# Challenger-2040.net
KiCad netlist of a schematic drawn in EAGLE
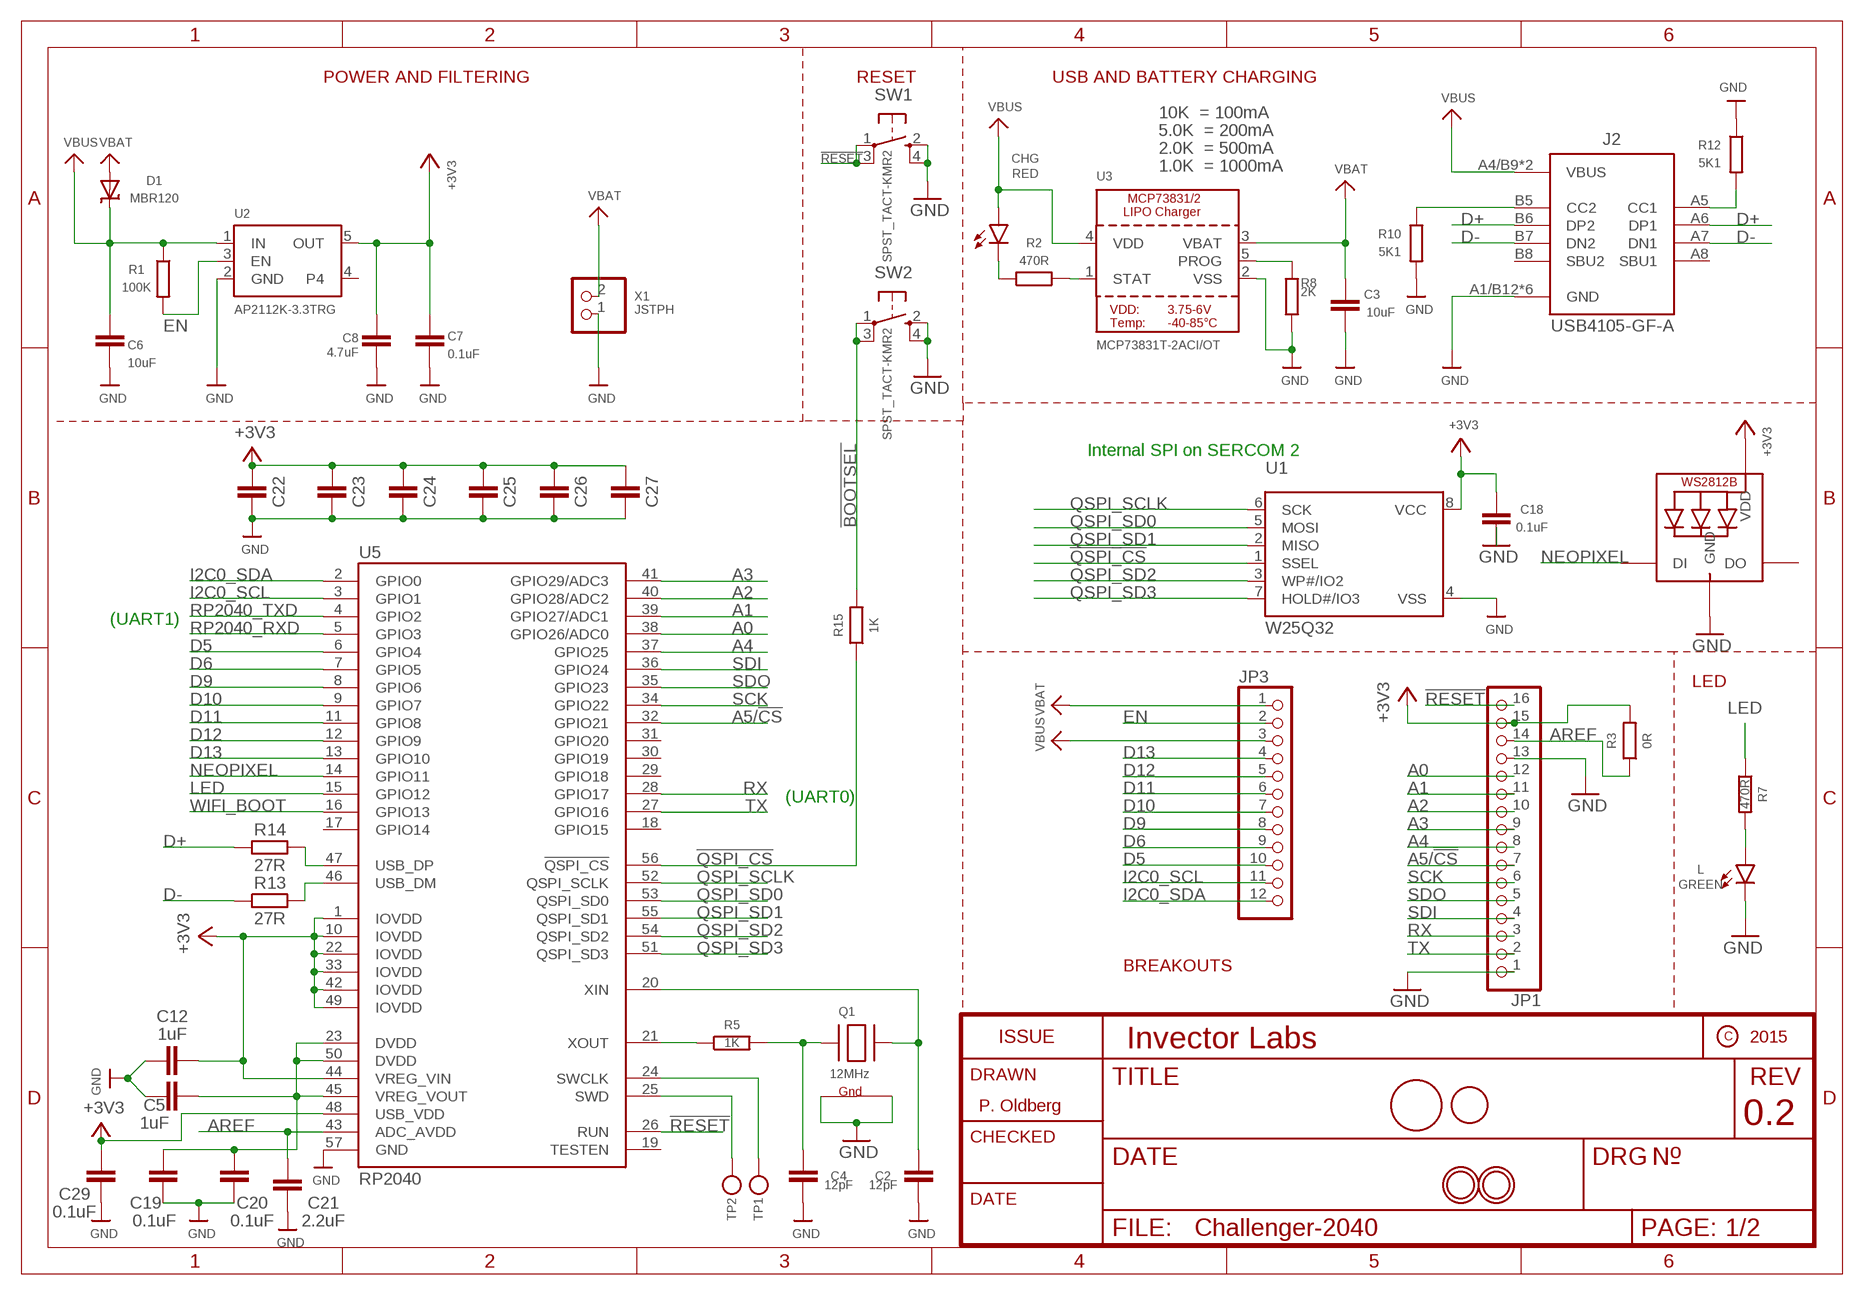
[diagram p0: schematic, sheet 1]
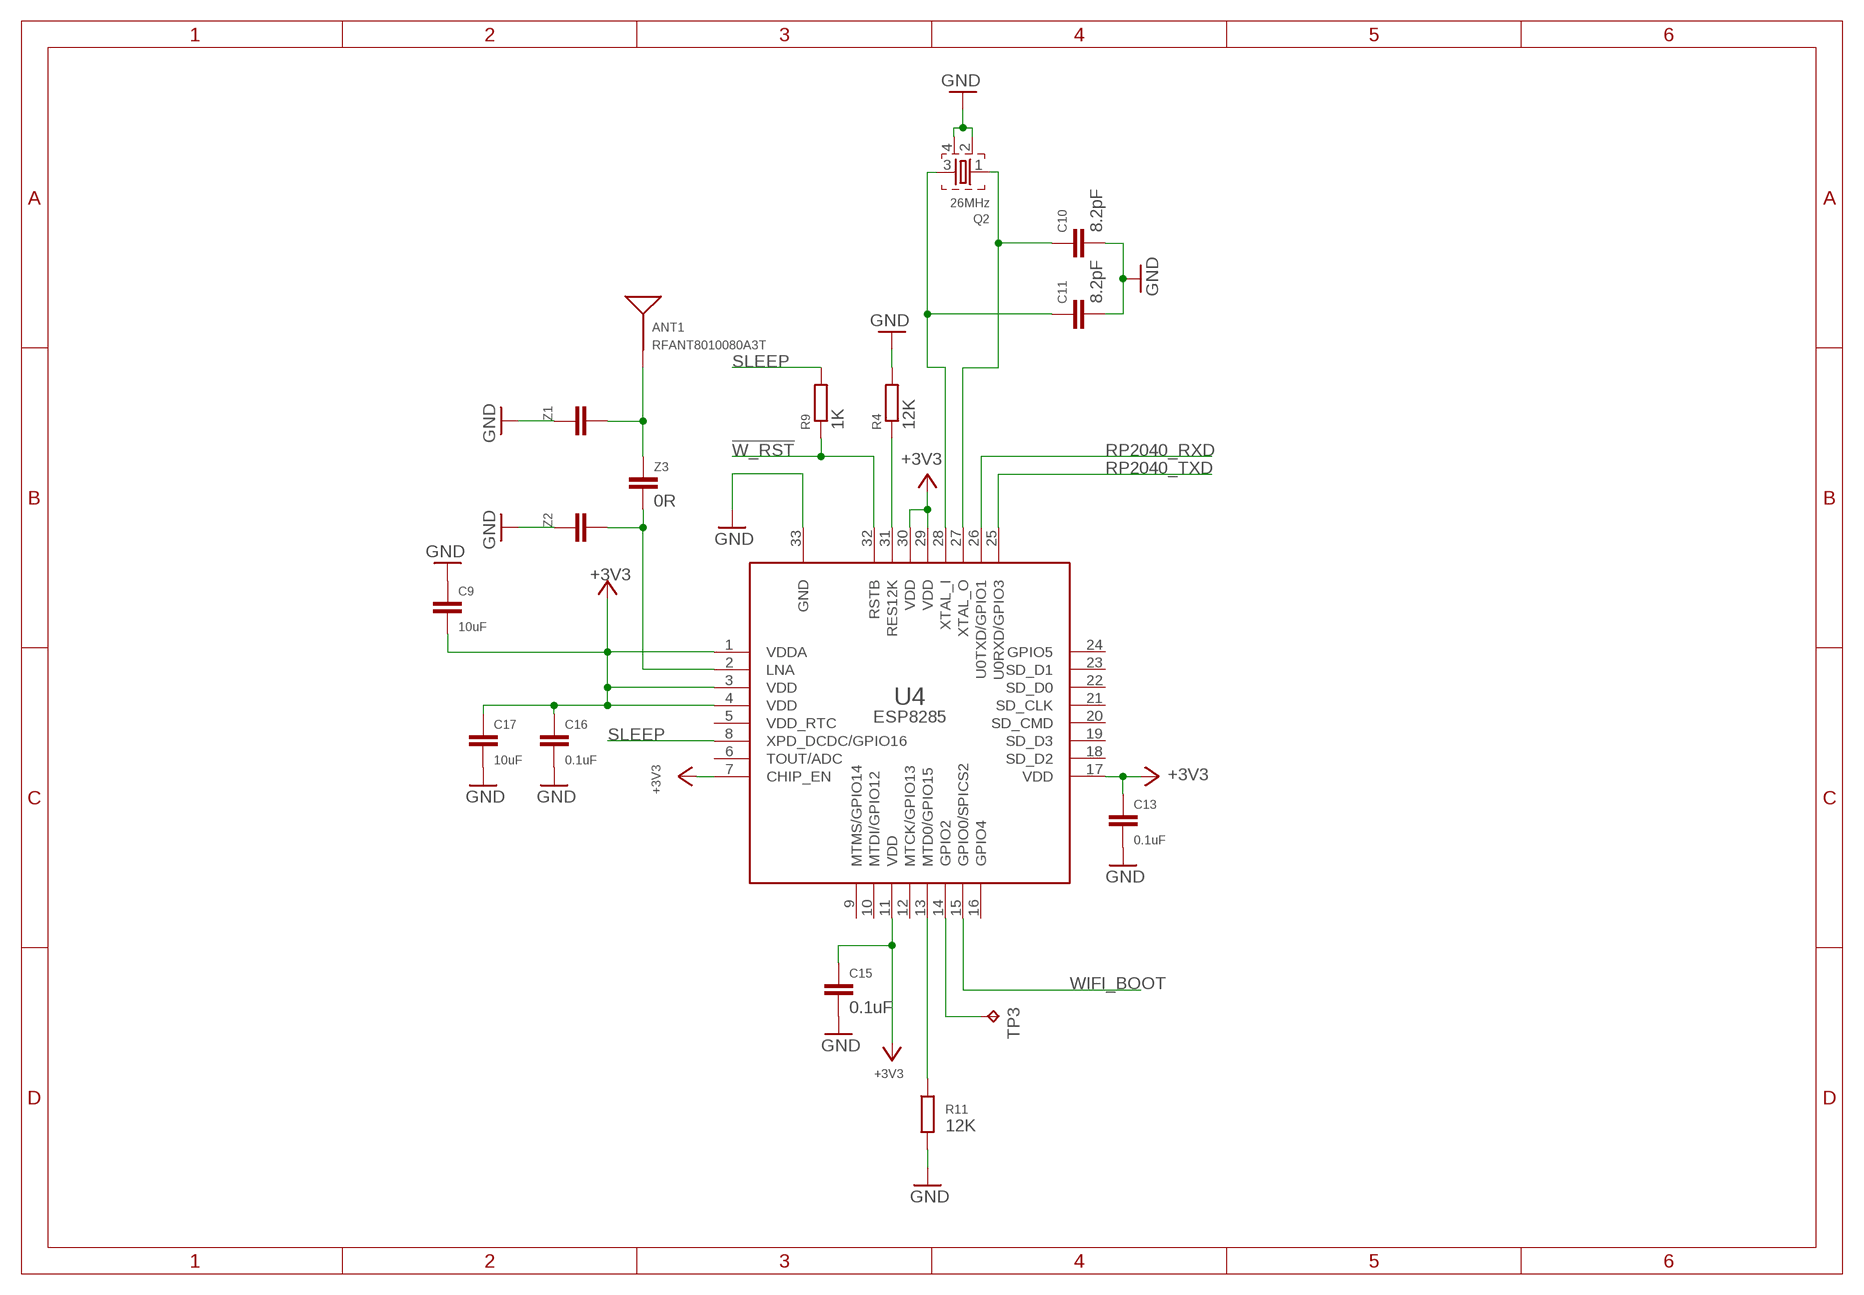
[diagram p1: schematic, sheet 2]

(export (version "E")
  (design (tool "Eeschema 10.0.6"))
  (components
    (comp (ref "ANT1")
      (value "RFANT8010080A3T")
      (footprint "eagle-import:ANTENNA-CHIP6")
      (libsource (lib "eagle-import") (part "ANTENNA2SMD6"))
    )
    (comp (ref "C9")
      (value "10uF")
      (footprint "eagle-import:CAPC1608X85")
      (libsource (lib "eagle-import") (part "CCHIP-0603(1608-METRIC)_"))
    )
    (comp (ref "C10")
      (value "8.2pF")
      (footprint "eagle-import:CAPC1005X60")
      (libsource (lib "eagle-import") (part "CCHIP-0402(1005-METRIC)_"))
    )
    (comp (ref "C11")
      (value "8.2pF")
      (footprint "eagle-import:CAPC1005X60")
      (libsource (lib "eagle-import") (part "CCHIP-0402(1005-METRIC)_"))
    )
    (comp (ref "C13")
      (value "0.1uF")
      (footprint "eagle-import:CAPC1005X60")
      (libsource (lib "eagle-import") (part "CCHIP-0402(1005-METRIC)_"))
    )
    (comp (ref "C15")
      (value "0.1uF")
      (footprint "eagle-import:CAPC1005X60")
      (libsource (lib "eagle-import") (part "CCHIP-0402(1005-METRIC)_"))
    )
    (comp (ref "C16")
      (value "0.1uF")
      (footprint "eagle-import:CAPC1005X60")
      (libsource (lib "eagle-import") (part "CCHIP-0402(1005-METRIC)_"))
    )
    (comp (ref "C17")
      (value "10uF")
      (footprint "eagle-import:CAPC1608X85")
      (libsource (lib "eagle-import") (part "CCHIP-0603(1608-METRIC)_"))
    )
    (comp (ref "Q2")
      (value "26MHz")
      (footprint "eagle-import:FA-128")
      (libsource (lib "eagle-import") (part "FA-128"))
    )
    (comp (ref "R4")
      (value "12K")
      (footprint "eagle-import:RESC1005X40")
      (libsource (lib "eagle-import") (part "RCHIP-0402(1005-METRIC)_"))
    )
    (comp (ref "R9")
      (value "1K")
      (footprint "eagle-import:RESC1005X40")
      (libsource (lib "eagle-import") (part "RCHIP-0402(1005-METRIC)_"))
    )
    (comp (ref "R11")
      (value "12K")
      (footprint "eagle-import:RESC1005X40")
      (libsource (lib "eagle-import") (part "RCHIP-0402(1005-METRIC)_"))
    )
    (comp (ref "TP3")
      (value "TPB1,27")
      (footprint "eagle-import:B1,27")
      (libsource (lib "eagle-import") (part "TPB1,27"))
    )
    (comp (ref "U4")
      (value "ESP8285")
      (footprint "eagle-import:SLP32")
      (libsource (lib "eagle-import") (part "ESP8266EXT"))
    )
    (comp (ref "Z1")
      (value "C_CHIP-0402(1005-METRIC)")
      (footprint "eagle-import:CAPC1005X60")
      (libsource (lib "eagle-import") (part "CCHIP-0402(1005-METRIC)_"))
    )
    (comp (ref "Z2")
      (value "C_CHIP-0402(1005-METRIC)")
      (footprint "eagle-import:CAPC1005X60")
      (libsource (lib "eagle-import") (part "CCHIP-0402(1005-METRIC)_"))
    )
    (comp (ref "Z3")
      (value "0R")
      (footprint "eagle-import:CAPC1005X60")
      (libsource (lib "eagle-import") (part "CCHIP-0402(1005-METRIC)_"))
    )
    (comp (ref "C2")
      (value "12pF")
      (footprint "eagle-import:CAPC1005X60")
      (libsource (lib "eagle-import") (part "CCHIP-0402(1005-METRIC)_"))
    )
    (comp (ref "C3")
      (value "10uF")
      (footprint "eagle-import:CAPC1608X85")
      (libsource (lib "eagle-import") (part "CCHIP-0603(1608-METRIC)_"))
    )
    (comp (ref "C4")
      (value "12pF")
      (footprint "eagle-import:CAPC1005X60")
      (libsource (lib "eagle-import") (part "CCHIP-0402(1005-METRIC)_"))
    )
    (comp (ref "C5")
      (value "1uF")
      (footprint "eagle-import:CAPC1005X60")
      (libsource (lib "eagle-import") (part "CCHIP-0402(1005-METRIC)_"))
    )
    (comp (ref "C6")
      (value "10uF")
      (footprint "eagle-import:CAPC1608X85")
      (libsource (lib "eagle-import") (part "CCHIP-0603(1608-METRIC)_"))
    )
    (comp (ref "C7")
      (value "0.1uF")
      (footprint "eagle-import:CAPC1005X60")
      (libsource (lib "eagle-import") (part "CCHIP-0402(1005-METRIC)_"))
    )
    (comp (ref "C8")
      (value "4.7uF")
      (footprint "eagle-import:CAPC1005X60")
      (libsource (lib "eagle-import") (part "CCHIP-0402(1005-METRIC)_"))
    )
    (comp (ref "C12")
      (value "1uF")
      (footprint "eagle-import:CAPC1005X60")
      (libsource (lib "eagle-import") (part "CCHIP-0402(1005-METRIC)_"))
    )
    (comp (ref "C18")
      (value "0.1uF")
      (footprint "eagle-import:CAPC1005X60")
      (libsource (lib "eagle-import") (part "CCHIP-0402(1005-METRIC)_"))
    )
    (comp (ref "C19")
      (value "0.1uF")
      (footprint "eagle-import:CAPC1005X60")
      (libsource (lib "eagle-import") (part "CCHIP-0402(1005-METRIC)_"))
    )
    (comp (ref "C20")
      (value "0.1uF")
      (footprint "eagle-import:CAPC1005X60")
      (libsource (lib "eagle-import") (part "CCHIP-0402(1005-METRIC)_"))
    )
    (comp (ref "C21")
      (value "2.2uF")
      (footprint "eagle-import:CAPC1005X60")
      (libsource (lib "eagle-import") (part "CCHIP-0402(1005-METRIC)_"))
    )
    (comp (ref "C22")
      (value "C_CHIP-0402(1005-METRIC)")
      (footprint "eagle-import:CAPC1005X60")
      (libsource (lib "eagle-import") (part "CCHIP-0402(1005-METRIC)_"))
    )
    (comp (ref "C23")
      (value "C_CHIP-0402(1005-METRIC)")
      (footprint "eagle-import:CAPC1005X60")
      (libsource (lib "eagle-import") (part "CCHIP-0402(1005-METRIC)_"))
    )
    (comp (ref "C24")
      (value "C_CHIP-0402(1005-METRIC)")
      (footprint "eagle-import:CAPC1005X60")
      (libsource (lib "eagle-import") (part "CCHIP-0402(1005-METRIC)_"))
    )
    (comp (ref "C25")
      (value "C_CHIP-0402(1005-METRIC)")
      (footprint "eagle-import:CAPC1005X60")
      (libsource (lib "eagle-import") (part "CCHIP-0402(1005-METRIC)_"))
    )
    (comp (ref "C26")
      (value "C_CHIP-0402(1005-METRIC)")
      (footprint "eagle-import:CAPC1005X60")
      (libsource (lib "eagle-import") (part "CCHIP-0402(1005-METRIC)_"))
    )
    (comp (ref "C27")
      (value "C_CHIP-0402(1005-METRIC)")
      (footprint "eagle-import:CAPC1005X60")
      (libsource (lib "eagle-import") (part "CCHIP-0402(1005-METRIC)_"))
    )
    (comp (ref "C29")
      (value "0.1uF")
      (footprint "eagle-import:CAPC1005X60")
      (libsource (lib "eagle-import") (part "CCHIP-0402(1005-METRIC)_"))
    )
    (comp (ref "CHG")
      (value "RED")
      (footprint "eagle-import:CHIPLED_0603")
      (libsource (lib "eagle-import") (part "LEDCHIPLED_0603"))
    )
    (comp (ref "D1")
      (value "MBR120")
      (footprint "eagle-import:SOD-123")
      (libsource (lib "eagle-import") (part "DIODE-SCHOTTKYSOD-123"))
    )
    (comp (ref "J2")
      (value "USB4105-GF-A")
      (footprint "eagle-import:GCT_USB4105-GF-A")
      (fields (field (name "MF") "GCT"))
      (libsource (lib "eagle-import") (part "USB4105-GF-A"))
    )
    (comp (ref "JP1")
      (value "HEADER-1X16ROUND")
      (footprint "eagle-import:1X16_ROUND")
      (libsource (lib "eagle-import") (part "HEADER-1X16ROUND"))
    )
    (comp (ref "JP3")
      (value "HEADER-1X12")
      (footprint "eagle-import:1X12_ROUND")
      (libsource (lib "eagle-import") (part "HEADER-1X12"))
    )
    (comp (ref "L")
      (value "GREEN")
      (footprint "eagle-import:CHIPLED_0603")
      (libsource (lib "eagle-import") (part "LEDCHIPLED_0603"))
    )
    (comp (ref "LED1")
      (value "WS2812B3535")
      (footprint "eagle-import:LED3535")
      (libsource (lib "eagle-import") (part "WS2812B3535"))
    )
    (comp (ref "LOGO1")
      (value "CHALENGER-11MM")
      (footprint "eagle-import:CHALLENGER")
      (libsource (lib "eagle-import") (part "CHALENGER-11MM"))
    )
    (comp (ref "Q1")
      (value "12MHz")
      (footprint "eagle-import:NX3225")
      (libsource (lib "eagle-import") (part "XTAL-4-3225"))
    )
    (comp (ref "R1")
      (value "100K")
      (footprint "eagle-import:RESC1005X40")
      (libsource (lib "eagle-import") (part "RCHIP-0402(1005-METRIC)_"))
    )
    (comp (ref "R2")
      (value "470R")
      (footprint "eagle-import:RESC1005X40")
      (libsource (lib "eagle-import") (part "RCHIP-0402(1005-METRIC)_"))
    )
    (comp (ref "R3")
      (value "0R")
      (footprint "eagle-import:RESC1005X40")
      (libsource (lib "eagle-import") (part "RCHIP-0402(1005-METRIC)_"))
    )
    (comp (ref "R5")
      (value "1K")
      (footprint "eagle-import:RESC1005X40")
      (libsource (lib "eagle-import") (part "RCHIP-0402(1005-METRIC)_"))
    )
    (comp (ref "R7")
      (value "470R")
      (footprint "eagle-import:RESC1005X40")
      (libsource (lib "eagle-import") (part "RCHIP-0402(1005-METRIC)_"))
    )
    (comp (ref "R8")
      (value "2K")
      (footprint "eagle-import:RESC1005X40")
      (libsource (lib "eagle-import") (part "RCHIP-0402(1005-METRIC)_"))
    )
    (comp (ref "R10")
      (value "5K1")
      (footprint "eagle-import:RESC1005X40")
      (libsource (lib "eagle-import") (part "RCHIP-0402(1005-METRIC)_"))
    )
    (comp (ref "R12")
      (value "5K1")
      (footprint "eagle-import:RESC1005X40")
      (libsource (lib "eagle-import") (part "RCHIP-0402(1005-METRIC)_"))
    )
    (comp (ref "R13")
      (value "27R")
      (footprint "eagle-import:RESC1005X40")
      (libsource (lib "eagle-import") (part "RCHIP-0402(1005-METRIC)_"))
    )
    (comp (ref "R14")
      (value "27R")
      (footprint "eagle-import:RESC1005X40")
      (libsource (lib "eagle-import") (part "RCHIP-0402(1005-METRIC)_"))
    )
    (comp (ref "R15")
      (value "1K")
      (footprint "eagle-import:RESC1005X40")
      (libsource (lib "eagle-import") (part "RCHIP-0402(1005-METRIC)_"))
    )
    (comp (ref "SW1")
      (value "SPST_TACT-KMR2")
      (footprint "eagle-import:KMR2")
      (libsource (lib "eagle-import") (part "SPST_TACT-KMR2"))
    )
    (comp (ref "SW2")
      (value "SPST_TACT-KMR2")
      (footprint "eagle-import:KMR2")
      (libsource (lib "eagle-import") (part "SPST_TACT-KMR2"))
    )
    (comp (ref "TP1")
      (value "TESTPOINTROUND1.5MM")
      (footprint "eagle-import:TESTPOINT_ROUND_1.5MM")
      (libsource (lib "eagle-import") (part "TESTPOINTROUND1.5MM"))
    )
    (comp (ref "TP2")
      (value "TESTPOINTROUND1.5MM")
      (footprint "eagle-import:TESTPOINT_ROUND_1.5MM")
      (libsource (lib "eagle-import") (part "TESTPOINTROUND1.5MM"))
    )
    (comp (ref "U$11")
      (value "CHAL-TEXT")
      (footprint "eagle-import:CHAL-TEXT")
      (libsource (lib "eagle-import") (part "CHAL-TEXT"))
    )
    (comp (ref "U$31")
      (value "MOUNTINGHOLE2.5")
      (footprint "eagle-import:MOUNTINGHOLE_2.5_PLATED")
      (libsource (lib "eagle-import") (part "MOUNTINGHOLE2.5"))
    )
    (comp (ref "U$32")
      (value "MOUNTINGHOLE2.5")
      (footprint "eagle-import:MOUNTINGHOLE_2.5_PLATED")
      (libsource (lib "eagle-import") (part "MOUNTINGHOLE2.5"))
    )
    (comp (ref "U1")
      (value "W25Q32")
      (footprint "eagle-import:SOIC8_208MIL")
      (libsource (lib "eagle-import") (part "SPIFLASH_SOIC8208MIL"))
    )
    (comp (ref "U2")
      (value "AP2112K-3.3TRG")
      (footprint "eagle-import:SOT23-5")
      (libsource (lib "eagle-import") (part "VREG_SOT23-5"))
    )
    (comp (ref "U3")
      (value "MCP73831T-2ACI/OT")
      (footprint "eagle-import:SOT23-5")
      (libsource (lib "eagle-import") (part "MCP73831/2"))
    )
    (comp (ref "U5")
      (value "RP2040")
      (footprint "eagle-import:QFN40P700X700X90-57T310N")
      (libsource (lib "eagle-import") (part "RP2040"))
    )
    (comp (ref "X1")
      (value "JSTPH")
      (footprint "eagle-import:JSTPH2")
      (libsource (lib "eagle-import") (part "CON_JST_PH_2PIN"))
    )
  )
  (nets
    (net (code "1") (name "+3V3") (class "Default")
      (node (ref "C12") (pin "2") (pinfunction "2_2") (pintype "passive"))
      (node (ref "C13") (pin "1") (pinfunction "1_1") (pintype "passive"))
      (node (ref "C15") (pin "1") (pinfunction "1_1") (pintype "passive"))
      (node (ref "C16") (pin "1") (pinfunction "1_1") (pintype "passive"))
      (node (ref "C17") (pin "1") (pinfunction "1_1") (pintype "passive"))
      (node (ref "C18") (pin "1") (pinfunction "1_1") (pintype "passive"))
      (node (ref "C22") (pin "2") (pinfunction "2_2") (pintype "passive"))
      (node (ref "C23") (pin "2") (pinfunction "2_2") (pintype "passive"))
      (node (ref "C24") (pin "2") (pinfunction "2_2") (pintype "passive"))
      (node (ref "C25") (pin "2") (pinfunction "2_2") (pintype "passive"))
      (node (ref "C26") (pin "2") (pinfunction "2_2") (pintype "passive"))
      (node (ref "C27") (pin "2") (pinfunction "2_2") (pintype "passive"))
      (node (ref "C29") (pin "2") (pinfunction "2_2") (pintype "passive"))
      (node (ref "C7") (pin "1") (pinfunction "1_1") (pintype "passive"))
      (node (ref "C8") (pin "1") (pinfunction "1_1") (pintype "passive"))
      (node (ref "C9") (pin "2") (pinfunction "2_2") (pintype "passive"))
      (node (ref "JP1") (pin "15") (pinfunction "15_15") (pintype "passive"))
      (node (ref "LED1") (pin "2") (pinfunction "VDD_2") (pintype "power_in"))
      (node (ref "R3") (pin "2") (pinfunction "2_2") (pintype "passive"))
      (node (ref "U1") (pin "8") (pinfunction "VCC_8") (pintype "bidirectional"))
      (node (ref "U2") (pin "5") (pinfunction "OUT_5") (pintype "power_in"))
      (node (ref "U4") (pin "1") (pinfunction "VDDA_1") (pintype "bidirectional"))
      (node (ref "U4") (pin "11") (pinfunction "VDD_11") (pintype "bidirectional"))
      (node (ref "U4") (pin "17") (pinfunction "VDD_17") (pintype "bidirectional"))
      (node (ref "U4") (pin "29") (pinfunction "VDD_29") (pintype "bidirectional"))
      (node (ref "U4") (pin "3") (pinfunction "VDD_3") (pintype "bidirectional"))
      (node (ref "U4") (pin "30") (pinfunction "VDD_30") (pintype "bidirectional"))
      (node (ref "U4") (pin "4") (pinfunction "VDD_4") (pintype "bidirectional"))
      (node (ref "U4") (pin "7") (pinfunction "CHIP_EN_7") (pintype "bidirectional"))
      (node (ref "U5") (pin "1") (pinfunction "IOVDD_1") (pintype "bidirectional"))
      (node (ref "U5") (pin "10") (pinfunction "IOVDD_10") (pintype "bidirectional"))
      (node (ref "U5") (pin "22") (pinfunction "IOVDD_22") (pintype "bidirectional"))
      (node (ref "U5") (pin "33") (pinfunction "IOVDD_33") (pintype "bidirectional"))
      (node (ref "U5") (pin "42") (pinfunction "IOVDD_42") (pintype "bidirectional"))
      (node (ref "U5") (pin "44") (pinfunction "VREG_VIN_44") (pintype "bidirectional"))
      (node (ref "U5") (pin "48") (pinfunction "USB_VDD_48") (pintype "bidirectional"))
      (node (ref "U5") (pin "49") (pinfunction "IOVDD_49") (pintype "bidirectional"))
    )
    (net (code "2") (name "A0") (class "Default")
      (node (ref "JP1") (pin "12") (pinfunction "12_12") (pintype "passive"))
      (node (ref "U5") (pin "38") (pinfunction "GPIO26/ADC0_38") (pintype "bidirectional"))
    )
    (net (code "3") (name "A1") (class "Default")
      (node (ref "JP1") (pin "11") (pinfunction "11_11") (pintype "passive"))
      (node (ref "U5") (pin "39") (pinfunction "GPIO27/ADC1_39") (pintype "bidirectional"))
    )
    (net (code "4") (name "A2") (class "Default")
      (node (ref "JP1") (pin "10") (pinfunction "10_10") (pintype "passive"))
      (node (ref "U5") (pin "40") (pinfunction "GPIO28/ADC2_40") (pintype "bidirectional"))
    )
    (net (code "5") (name "A3") (class "Default")
      (node (ref "JP1") (pin "9") (pinfunction "9_9") (pintype "passive"))
      (node (ref "U5") (pin "41") (pinfunction "GPIO29/ADC3_41") (pintype "bidirectional"))
    )
    (net (code "6") (name "A4") (class "Default")
      (node (ref "JP1") (pin "8") (pinfunction "8_8") (pintype "passive"))
      (node (ref "U5") (pin "37") (pinfunction "GPIO25_37") (pintype "bidirectional"))
    )
    (net (code "7") (name "A5{slash}~{CS}") (class "Default")
      (node (ref "JP1") (pin "7") (pinfunction "7_7") (pintype "passive"))
      (node (ref "U5") (pin "32") (pinfunction "GPIO21_32") (pintype "bidirectional"))
    )
    (net (code "8") (name "AREF") (class "Default")
      (node (ref "C21") (pin "2") (pinfunction "2_2") (pintype "passive"))
      (node (ref "JP1") (pin "14") (pinfunction "14_14") (pintype "passive"))
      (node (ref "R3") (pin "1") (pinfunction "1_1") (pintype "passive"))
      (node (ref "U5") (pin "43") (pinfunction "ADC_AVDD_43") (pintype "bidirectional"))
    )
    (net (code "9") (name "D+") (class "Default")
      (node (ref "J2") (pin "A6") (pinfunction "DP1_A6") (pintype "bidirectional"))
      (node (ref "J2") (pin "B6") (pinfunction "DP2_B6") (pintype "bidirectional"))
      (node (ref "R14") (pin "1") (pinfunction "1_1") (pintype "passive"))
    )
    (net (code "10") (name "D-") (class "Default")
      (node (ref "J2") (pin "A7") (pinfunction "DN1_A7") (pintype "bidirectional"))
      (node (ref "J2") (pin "B7") (pinfunction "DN2_B7") (pintype "bidirectional"))
      (node (ref "R13") (pin "1") (pinfunction "1_1") (pintype "passive"))
    )
    (net (code "11") (name "D5") (class "Default")
      (node (ref "JP3") (pin "10") (pinfunction "10_10") (pintype "passive"))
      (node (ref "U5") (pin "6") (pinfunction "GPIO4_6") (pintype "bidirectional"))
    )
    (net (code "12") (name "D6") (class "Default")
      (node (ref "JP3") (pin "9") (pinfunction "9_9") (pintype "passive"))
      (node (ref "U5") (pin "7") (pinfunction "GPIO5_7") (pintype "bidirectional"))
    )
    (net (code "13") (name "D9") (class "Default")
      (node (ref "JP3") (pin "8") (pinfunction "8_8") (pintype "passive"))
      (node (ref "U5") (pin "8") (pinfunction "GPIO6_8") (pintype "bidirectional"))
    )
    (net (code "14") (name "D10") (class "Default")
      (node (ref "JP3") (pin "7") (pinfunction "7_7") (pintype "passive"))
      (node (ref "U5") (pin "9") (pinfunction "GPIO7_9") (pintype "bidirectional"))
    )
    (net (code "15") (name "D11") (class "Default")
      (node (ref "JP3") (pin "6") (pinfunction "6_6") (pintype "passive"))
      (node (ref "U5") (pin "11") (pinfunction "GPIO8_11") (pintype "bidirectional"))
    )
    (net (code "16") (name "D12") (class "Default")
      (node (ref "JP3") (pin "5") (pinfunction "5_5") (pintype "passive"))
      (node (ref "U5") (pin "12") (pinfunction "GPIO9_12") (pintype "bidirectional"))
    )
    (net (code "17") (name "D13") (class "Default")
      (node (ref "JP3") (pin "4") (pinfunction "4_4") (pintype "passive"))
      (node (ref "U5") (pin "13") (pinfunction "GPIO10_13") (pintype "bidirectional"))
    )
    (net (code "18") (name "EN") (class "Default")
      (node (ref "JP3") (pin "2") (pinfunction "2_2") (pintype "passive"))
      (node (ref "R1") (pin "2") (pinfunction "2_2") (pintype "passive"))
      (node (ref "U2") (pin "3") (pinfunction "EN_3") (pintype "input"))
    )
    (net (code "19") (name "GND") (class "Default")
      (node (ref "C10") (pin "2") (pinfunction "2_2") (pintype "passive"))
      (node (ref "C11") (pin "2") (pinfunction "2_2") (pintype "passive"))
      (node (ref "C12") (pin "1") (pinfunction "1_1") (pintype "passive"))
      (node (ref "C13") (pin "2") (pinfunction "2_2") (pintype "passive"))
      (node (ref "C15") (pin "2") (pinfunction "2_2") (pintype "passive"))
      (node (ref "C16") (pin "2") (pinfunction "2_2") (pintype "passive"))
      (node (ref "C17") (pin "2") (pinfunction "2_2") (pintype "passive"))
      (node (ref "C18") (pin "2") (pinfunction "2_2") (pintype "passive"))
      (node (ref "C19") (pin "1") (pinfunction "1_1") (pintype "passive"))
      (node (ref "C2") (pin "2") (pinfunction "2_2") (pintype "passive"))
      (node (ref "C20") (pin "1") (pinfunction "1_1") (pintype "passive"))
      (node (ref "C21") (pin "1") (pinfunction "1_1") (pintype "passive"))
      (node (ref "C22") (pin "1") (pinfunction "1_1") (pintype "passive"))
      (node (ref "C23") (pin "1") (pinfunction "1_1") (pintype "passive"))
      (node (ref "C24") (pin "1") (pinfunction "1_1") (pintype "passive"))
      (node (ref "C25") (pin "1") (pinfunction "1_1") (pintype "passive"))
      (node (ref "C26") (pin "1") (pinfunction "1_1") (pintype "passive"))
      (node (ref "C27") (pin "1") (pinfunction "1_1") (pintype "passive"))
      (node (ref "C29") (pin "1") (pinfunction "1_1") (pintype "passive"))
      (node (ref "C3") (pin "2") (pinfunction "2_2") (pintype "passive"))
      (node (ref "C4") (pin "2") (pinfunction "2_2") (pintype "passive"))
      (node (ref "C5") (pin "1") (pinfunction "1_1") (pintype "passive"))
      (node (ref "C6") (pin "2") (pinfunction "2_2") (pintype "passive"))
      (node (ref "C7") (pin "2") (pinfunction "2_2") (pintype "passive"))
      (node (ref "C8") (pin "2") (pinfunction "2_2") (pintype "passive"))
      (node (ref "C9") (pin "1") (pinfunction "1_1") (pintype "passive"))
      (node (ref "J2") (pin "A1/B12") (pinfunction "GND_A1/B12") (pintype "power_in"))
      (node (ref "J2") (pin "B1/A12") (pinfunction "GND_B1/A12") (pintype "power_in"))
      (node (ref "J2") (pin "G1") (pinfunction "GND_G1") (pintype "power_in"))
      (node (ref "J2") (pin "G2") (pinfunction "GND_G2") (pintype "power_in"))
      (node (ref "J2") (pin "G3") (pinfunction "GND_G3") (pintype "power_in"))
      (node (ref "J2") (pin "G4") (pinfunction "GND_G4") (pintype "power_in"))
      (node (ref "JP1") (pin "1") (pinfunction "1_1") (pintype "passive"))
      (node (ref "JP1") (pin "13") (pinfunction "13_13") (pintype "passive"))
      (node (ref "L") (pin "C") (pinfunction "C_C") (pintype "passive"))
      (node (ref "LED1") (pin "4") (pinfunction "GND_4") (pintype "power_in"))
      (node (ref "Q1") (pin "2") (pinfunction "G2_2") (pintype "power_in"))
      (node (ref "Q1") (pin "4") (pinfunction "G1_4") (pintype "power_in"))
      (node (ref "Q2") (pin "2") (pinfunction "2_2") (pintype "passive"))
      (node (ref "Q2") (pin "4") (pinfunction "4_4") (pintype "passive"))
      (node (ref "R10") (pin "2") (pinfunction "2_2") (pintype "passive"))
      (node (ref "R11") (pin "2") (pinfunction "2_2") (pintype "passive"))
      (node (ref "R12") (pin "1") (pinfunction "1_1") (pintype "passive"))
      (node (ref "R4") (pin "2") (pinfunction "2_2") (pintype "passive"))
      (node (ref "R8") (pin "2") (pinfunction "2_2") (pintype "passive"))
      (node (ref "SW1") (pin "2") (pinfunction "S_2") (pintype "passive"))
      (node (ref "SW1") (pin "4") (pinfunction "S1_4") (pintype "passive"))
      (node (ref "SW2") (pin "2") (pinfunction "S_2") (pintype "passive"))
      (node (ref "SW2") (pin "4") (pinfunction "S1_4") (pintype "passive"))
      (node (ref "U1") (pin "4") (pinfunction "VSS_4") (pintype "bidirectional"))
      (node (ref "U2") (pin "2") (pinfunction "GND_2") (pintype "power_in"))
      (node (ref "U3") (pin "2") (pinfunction "VSS_2") (pintype "power_in"))
      (node (ref "U4") (pin "33") (pinfunction "GND_33") (pintype "bidirectional"))
      (node (ref "U5") (pin "57") (pinfunction "GND_57") (pintype "bidirectional"))
      (node (ref "X1") (pin "1") (pinfunction "1_1") (pintype "passive"))
      (node (ref "Z1") (pin "1") (pinfunction "1_1") (pintype "passive"))
      (node (ref "Z2") (pin "1") (pinfunction "1_1") (pintype "passive"))
    )
    (net (code "20") (name "I2C0_SCL") (class "Default")
      (node (ref "JP3") (pin "11") (pinfunction "11_11") (pintype "passive"))
      (node (ref "U5") (pin "3") (pinfunction "GPIO1_3") (pintype "bidirectional"))
    )
    (net (code "21") (name "I2C0_SDA") (class "Default")
      (node (ref "JP3") (pin "12") (pinfunction "12_12") (pintype "passive"))
      (node (ref "U5") (pin "2") (pinfunction "GPIO0_2") (pintype "bidirectional"))
    )
    (net (code "22") (name "LED") (class "Default")
      (node (ref "R7") (pin "1") (pinfunction "1_1") (pintype "passive"))
      (node (ref "U5") (pin "15") (pinfunction "GPIO12_15") (pintype "bidirectional"))
    )
    (net (code "23") (name "NEOPIXEL") (class "Default")
      (node (ref "LED1") (pin "1") (pinfunction "DI_1") (pintype "input"))
      (node (ref "U5") (pin "14") (pinfunction "GPIO11_14") (pintype "bidirectional"))
    )
    (net (code "24") (name "Net-(ANT1-SIGNAL)") (class "Default")
      (node (ref "ANT1") (pin "1") (pinfunction "SIGNAL_1") (pintype "bidirectional"))
      (node (ref "Z1") (pin "2") (pinfunction "2_2") (pintype "passive"))
      (node (ref "Z3") (pin "1") (pinfunction "1_1") (pintype "passive"))
    )
    (net (code "25") (name "Net-(CHG-PadC)") (class "Default")
      (node (ref "CHG") (pin "C") (pinfunction "C_C") (pintype "passive"))
      (node (ref "R2") (pin "1") (pinfunction "1_1") (pintype "passive"))
    )
    (net (code "26") (name "Net-(J2-CC1)") (class "Default")
      (node (ref "J2") (pin "A5") (pinfunction "CC1_A5") (pintype "bidirectional"))
      (node (ref "R12") (pin "2") (pinfunction "2_2") (pintype "passive"))
    )
    (net (code "27") (name "Net-(J2-CC2)") (class "Default")
      (node (ref "J2") (pin "B5") (pinfunction "CC2_B5") (pintype "bidirectional"))
      (node (ref "R10") (pin "1") (pinfunction "1_1") (pintype "passive"))
    )
    (net (code "28") (name "Net-(L-PadA)") (class "Default")
      (node (ref "L") (pin "A") (pinfunction "A_A") (pintype "passive"))
      (node (ref "R7") (pin "2") (pinfunction "2_2") (pintype "passive"))
    )
    (net (code "29") (name "Net-(Q1-X1)") (class "Default")
      (node (ref "C4") (pin "1") (pinfunction "1_1") (pintype "passive"))
      (node (ref "Q1") (pin "1") (pinfunction "X1_1") (pintype "bidirectional"))
      (node (ref "R5") (pin "2") (pinfunction "2_2") (pintype "passive"))
    )
    (net (code "30") (name "Net-(Q1-X2)") (class "Default")
      (node (ref "C2") (pin "1") (pinfunction "1_1") (pintype "passive"))
      (node (ref "Q1") (pin "3") (pinfunction "X2_3") (pintype "bidirectional"))
      (node (ref "U5") (pin "20") (pinfunction "XIN_20") (pintype "bidirectional"))
    )
    (net (code "31") (name "Net-(U3-PROG)") (class "Default")
      (node (ref "R8") (pin "1") (pinfunction "1_1") (pintype "passive"))
      (node (ref "U3") (pin "5") (pinfunction "PROG_5") (pintype "input"))
    )
    (net (code "32") (name "Net-(U3-STAT)") (class "Default")
      (node (ref "R2") (pin "2") (pinfunction "2_2") (pintype "passive"))
      (node (ref "U3") (pin "1") (pinfunction "STAT_1") (pintype "output"))
    )
    (net (code "33") (name "Net-(U4-GPIO2)") (class "Default")
      (node (ref "TP3") (pin "TP") (pinfunction "TP_TP") (pintype "input"))
      (node (ref "U4") (pin "14") (pinfunction "GPIO2_14") (pintype "bidirectional"))
    )
    (net (code "34") (name "Net-(U4-LNA)") (class "Default")
      (node (ref "U4") (pin "2") (pinfunction "LNA_2") (pintype "bidirectional"))
      (node (ref "Z2") (pin "2") (pinfunction "2_2") (pintype "passive"))
      (node (ref "Z3") (pin "2") (pinfunction "2_2") (pintype "passive"))
    )
    (net (code "35") (name "Net-(U4-MTD0{slash}GPIO15)") (class "Default")
      (node (ref "R11") (pin "1") (pinfunction "1_1") (pintype "passive"))
      (node (ref "U4") (pin "13") (pinfunction "MTD0/GPIO15_13") (pintype "bidirectional"))
    )
    (net (code "36") (name "Net-(U4-RES12K)") (class "Default")
      (node (ref "R4") (pin "1") (pinfunction "1_1") (pintype "passive"))
      (node (ref "U4") (pin "31") (pinfunction "RES12K_31") (pintype "bidirectional"))
    )
    (net (code "37") (name "Net-(U4-XTAL_I)") (class "Default")
      (node (ref "C11") (pin "1") (pinfunction "1_1") (pintype "passive"))
      (node (ref "Q2") (pin "3") (pinfunction "3_3") (pintype "passive"))
      (node (ref "U4") (pin "28") (pinfunction "XTAL_I_28") (pintype "bidirectional"))
    )
    (net (code "38") (name "Net-(U4-XTAL_O)") (class "Default")
      (node (ref "C10") (pin "1") (pinfunction "1_1") (pintype "passive"))
      (node (ref "Q2") (pin "1") (pinfunction "1_1") (pintype "passive"))
      (node (ref "U4") (pin "27") (pinfunction "XTAL_O_27") (pintype "bidirectional"))
    )
    (net (code "39") (name "Net-(U5-SWCLK)") (class "Default")
      (node (ref "TP1") (pin "P$1") (pinfunction "P$1_P$1") (pintype "bidirectional"))
      (node (ref "U5") (pin "24") (pinfunction "SWCLK_24") (pintype "bidirectional"))
    )
    (net (code "40") (name "Net-(U5-SWD)") (class "Default")
      (node (ref "TP2") (pin "P$1") (pinfunction "P$1_P$1") (pintype "bidirectional"))
      (node (ref "U5") (pin "25") (pinfunction "SWD_25") (pintype "bidirectional"))
    )
    (net (code "41") (name "Net-(U5-USB_DM)") (class "Default")
      (node (ref "R13") (pin "2") (pinfunction "2_2") (pintype "passive"))
      (node (ref "U5") (pin "46") (pinfunction "USB_DM_46") (pintype "bidirectional"))
    )
    (net (code "42") (name "Net-(U5-USB_DP)") (class "Default")
      (node (ref "R14") (pin "2") (pinfunction "2_2") (pintype "passive"))
      (node (ref "U5") (pin "47") (pinfunction "USB_DP_47") (pintype "bidirectional"))
    )
    (net (code "43") (name "Net-(U5-VREG_VOUT)") (class "Default")
      (node (ref "C19") (pin "2") (pinfunction "2_2") (pintype "passive"))
      (node (ref "C20") (pin "2") (pinfunction "2_2") (pintype "passive"))
      (node (ref "C5") (pin "2") (pinfunction "2_2") (pintype "passive"))
      (node (ref "U5") (pin "23") (pinfunction "DVDD_23") (pintype "bidirectional"))
      (node (ref "U5") (pin "45") (pinfunction "VREG_VOUT_45") (pintype "bidirectional"))
      (node (ref "U5") (pin "50") (pinfunction "DVDD_50") (pintype "bidirectional"))
    )
    (net (code "44") (name "Net-(U5-XOUT)") (class "Default")
      (node (ref "R5") (pin "1") (pinfunction "1_1") (pintype "passive"))
      (node (ref "U5") (pin "21") (pinfunction "XOUT_21") (pintype "bidirectional"))
    )
    (net (code "45") (name "QSPI_SCLK") (class "Default")
      (node (ref "U1") (pin "6") (pinfunction "SCK_6") (pintype "bidirectional"))
      (node (ref "U5") (pin "52") (pinfunction "QSPI_SCLK_52") (pintype "bidirectional"))
    )
    (net (code "46") (name "QSPI_SD0") (class "Default")
      (node (ref "U1") (pin "5") (pinfunction "MOSI_5") (pintype "bidirectional"))
      (node (ref "U5") (pin "53") (pinfunction "QSPI_SD0_53") (pintype "bidirectional"))
    )
    (net (code "47") (name "QSPI_SD1") (class "Default")
      (node (ref "U1") (pin "2") (pinfunction "MISO_2") (pintype "bidirectional"))
      (node (ref "U5") (pin "55") (pinfunction "QSPI_SD1_55") (pintype "bidirectional"))
    )
    (net (code "48") (name "QSPI_SD2") (class "Default")
      (node (ref "U1") (pin "3") (pinfunction "WP#/IO2_3") (pintype "bidirectional"))
      (node (ref "U5") (pin "54") (pinfunction "QSPI_SD2_54") (pintype "bidirectional"))
    )
    (net (code "49") (name "QSPI_SD3") (class "Default")
      (node (ref "U1") (pin "7") (pinfunction "HOLD#/IO3_7") (pintype "bidirectional"))
      (node (ref "U5") (pin "51") (pinfunction "QSPI_SD3_51") (pintype "bidirectional"))
    )
    (net (code "50") (name "RP2040_RXD") (class "Default")
      (node (ref "U4") (pin "26") (pinfunction "U0TXD/GPIO1_26") (pintype "bidirectional"))
      (node (ref "U5") (pin "5") (pinfunction "GPIO3_5") (pintype "bidirectional"))
    )
    (net (code "51") (name "RP2040_TXD") (class "Default")
      (node (ref "U4") (pin "25") (pinfunction "U0RXD/GPIO3_25") (pintype "bidirectional"))
      (node (ref "U5") (pin "4") (pinfunction "GPIO2_4") (pintype "bidirectional"))
    )
    (net (code "52") (name "RX") (class "Default")
      (node (ref "JP1") (pin "3") (pinfunction "3_3") (pintype "passive"))
      (node (ref "U5") (pin "28") (pinfunction "GPIO17_28") (pintype "bidirectional"))
    )
    (net (code "53") (name "SCK") (class "Default")
      (node (ref "JP1") (pin "6") (pinfunction "6_6") (pintype "passive"))
      (node (ref "U5") (pin "34") (pinfunction "GPIO22_34") (pintype "bidirectional"))
    )
    (net (code "54") (name "SDI") (class "Default")
      (node (ref "JP1") (pin "4") (pinfunction "4_4") (pintype "passive"))
      (node (ref "U5") (pin "36") (pinfunction "GPIO24_36") (pintype "bidirectional"))
    )
    (net (code "55") (name "SDO") (class "Default")
      (node (ref "JP1") (pin "5") (pinfunction "5_5") (pintype "passive"))
      (node (ref "U5") (pin "35") (pinfunction "GPIO23_35") (pintype "bidirectional"))
    )
    (net (code "56") (name "SLEEP") (class "Default")
      (node (ref "R9") (pin "2") (pinfunction "2_2") (pintype "passive"))
      (node (ref "U4") (pin "8") (pinfunction "XPD_DCDC/GPIO16_8") (pintype "bidirectional"))
    )
    (net (code "57") (name "TX") (class "Default")
      (node (ref "JP1") (pin "2") (pinfunction "2_2") (pintype "passive"))
      (node (ref "U5") (pin "27") (pinfunction "GPIO16_27") (pintype "bidirectional"))
    )
    (net (code "58") (name "VBAT") (class "Default")
      (node (ref "C3") (pin "1") (pinfunction "1_1") (pintype "passive"))
      (node (ref "D1") (pin "A") (pinfunction "A_A") (pintype "passive"))
      (node (ref "JP3") (pin "1") (pinfunction "1_1") (pintype "passive"))
      (node (ref "U3") (pin "3") (pinfunction "VBAT_3") (pintype "power_in"))
      (node (ref "X1") (pin "2") (pinfunction "2_2") (pintype "passive"))
    )
    (net (code "59") (name "VBUS") (class "Default")
      (node (ref "C6") (pin "1") (pinfunction "1_1") (pintype "passive"))
      (node (ref "CHG") (pin "A") (pinfunction "A_A") (pintype "passive"))
      (node (ref "D1") (pin "C") (pinfunction "C_C") (pintype "passive"))
      (node (ref "J2") (pin "A4/B9") (pinfunction "VBUS_A4/B9") (pintype "power_in"))
      (node (ref "J2") (pin "B4/A9") (pinfunction "VBUS_B4/A9") (pintype "power_in"))
      (node (ref "JP3") (pin "3") (pinfunction "3_3") (pintype "passive"))
      (node (ref "R1") (pin "1") (pinfunction "1_1") (pintype "passive"))
      (node (ref "U2") (pin "1") (pinfunction "IN_1") (pintype "power_in"))
      (node (ref "U3") (pin "4") (pinfunction "VDD_4") (pintype "power_in"))
    )
    (net (code "60") (name "WIFI_BOOT") (class "Default")
      (node (ref "U4") (pin "15") (pinfunction "GPIO0/SPICS2_15") (pintype "bidirectional"))
      (node (ref "U5") (pin "16") (pinfunction "GPIO13_16") (pintype "bidirectional"))
    )
    (net (code "61") (name "unconnected-(J2-SBU1-PadA8)") (class "Default")
      (node (ref "J2") (pin "A8") (pinfunction "SBU1_A8") (pintype "bidirectional"))
    )
    (net (code "62") (name "unconnected-(J2-SBU2-PadB8)") (class "Default")
      (node (ref "J2") (pin "B8") (pinfunction "SBU2_B8") (pintype "bidirectional"))
    )
    (net (code "63") (name "unconnected-(LED1-DO-Pad3)") (class "Default")
      (node (ref "LED1") (pin "3") (pinfunction "DO_3") (pintype "output"))
    )
    (net (code "64") (name "unconnected-(U2-P4-Pad4)") (class "Default")
      (node (ref "U2") (pin "4") (pinfunction "P4_4") (pintype "bidirectional"))
    )
    (net (code "65") (name "unconnected-(U4-GPIO4-Pad16)") (class "Default")
      (node (ref "U4") (pin "16") (pinfunction "GPIO4_16") (pintype "bidirectional"))
    )
    (net (code "66") (name "unconnected-(U4-GPIO5-Pad24)") (class "Default")
      (node (ref "U4") (pin "24") (pinfunction "GPIO5_24") (pintype "bidirectional"))
    )
    (net (code "67") (name "unconnected-(U4-MTCK{slash}GPIO13-Pad12)") (class "Default")
      (node (ref "U4") (pin "12") (pinfunction "MTCK/GPIO13_12") (pintype "bidirectional"))
    )
    (net (code "68") (name "unconnected-(U4-MTDI{slash}GPIO12-Pad10)") (class "Default")
      (node (ref "U4") (pin "10") (pinfunction "MTDI/GPIO12_10") (pintype "bidirectional"))
    )
    (net (code "69") (name "unconnected-(U4-MTMS{slash}GPIO14-Pad9)") (class "Default")
      (node (ref "U4") (pin "9") (pinfunction "MTMS/GPIO14_9") (pintype "bidirectional"))
    )
    (net (code "70") (name "unconnected-(U4-SD_CLK-Pad21)") (class "Default")
      (node (ref "U4") (pin "21") (pinfunction "SD_CLK_21") (pintype "bidirectional"))
    )
    (net (code "71") (name "unconnected-(U4-SD_CMD-Pad20)") (class "Default")
      (node (ref "U4") (pin "20") (pinfunction "SD_CMD_20") (pintype "bidirectional"))
    )
    (net (code "72") (name "unconnected-(U4-SD_D0-Pad22)") (class "Default")
      (node (ref "U4") (pin "22") (pinfunction "SD_D0_22") (pintype "bidirectional"))
    )
    (net (code "73") (name "unconnected-(U4-SD_D1-Pad23)") (class "Default")
      (node (ref "U4") (pin "23") (pinfunction "SD_D1_23") (pintype "bidirectional"))
    )
    (net (code "74") (name "unconnected-(U4-SD_D2-Pad18)") (class "Default")
      (node (ref "U4") (pin "18") (pinfunction "SD_D2_18") (pintype "bidirectional"))
    )
    (net (code "75") (name "unconnected-(U4-SD_D3-Pad19)") (class "Default")
      (node (ref "U4") (pin "19") (pinfunction "SD_D3_19") (pintype "bidirectional"))
    )
    (net (code "76") (name "unconnected-(U4-TOUT{slash}ADC-Pad6)") (class "Default")
      (node (ref "U4") (pin "6") (pinfunction "TOUT/ADC_6") (pintype "bidirectional"))
    )
    (net (code "77") (name "unconnected-(U4-VDD_RTC-Pad5)") (class "Default")
      (node (ref "U4") (pin "5") (pinfunction "VDD_RTC_5") (pintype "bidirectional"))
    )
    (net (code "78") (name "unconnected-(U5-GPIO14-Pad17)") (class "Default")
      (node (ref "U5") (pin "17") (pinfunction "GPIO14_17") (pintype "bidirectional"))
    )
    (net (code "79") (name "unconnected-(U5-GPIO15-Pad18)") (class "Default")
      (node (ref "U5") (pin "18") (pinfunction "GPIO15_18") (pintype "bidirectional"))
    )
    (net (code "80") (name "unconnected-(U5-GPIO18-Pad29)") (class "Default")
      (node (ref "U5") (pin "29") (pinfunction "GPIO18_29") (pintype "bidirectional"))
    )
    (net (code "81") (name "unconnected-(U5-GPIO19-Pad30)") (class "Default")
      (node (ref "U5") (pin "30") (pinfunction "GPIO19_30") (pintype "bidirectional"))
    )
    (net (code "82") (name "unconnected-(U5-GPIO20-Pad31)") (class "Default")
      (node (ref "U5") (pin "31") (pinfunction "GPIO20_31") (pintype "bidirectional"))
    )
    (net (code "83") (name "unconnected-(U5-TESTEN-Pad19)") (class "Default")
      (node (ref "U5") (pin "19") (pinfunction "TESTEN_19") (pintype "bidirectional"))
    )
    (net (code "84") (name "~{BOOTSEL}") (class "Default")
      (node (ref "R15") (pin "2") (pinfunction "2_2") (pintype "passive"))
      (node (ref "SW2") (pin "1") (pinfunction "P_1") (pintype "passive"))
      (node (ref "SW2") (pin "3") (pinfunction "P1_3") (pintype "passive"))
    )
    (net (code "85") (name "~{QSPI_CS}") (class "Default")
      (node (ref "R15") (pin "1") (pinfunction "1_1") (pintype "passive"))
      (node (ref "U1") (pin "1") (pinfunction "SSEL_1") (pintype "bidirectional"))
      (node (ref "U5") (pin "56") (pinfunction "~{QSPI_CS}_56") (pintype "bidirectional"))
    )
    (net (code "86") (name "~{RESET}") (class "Default")
      (node (ref "JP1") (pin "16") (pinfunction "16_16") (pintype "passive"))
      (node (ref "SW1") (pin "1") (pinfunction "P_1") (pintype "passive"))
      (node (ref "SW1") (pin "3") (pinfunction "P1_3") (pintype "passive"))
      (node (ref "U5") (pin "26") (pinfunction "RUN_26") (pintype "bidirectional"))
    )
    (net (code "87") (name "~{W_RST}") (class "Default")
      (node (ref "R9") (pin "1") (pinfunction "1_1") (pintype "passive"))
      (node (ref "U4") (pin "32") (pinfunction "RSTB_32") (pintype "bidirectional"))
    )
  )
)
